# stm32_usbserial.net
KiCad netlist of a schematic drawn in EAGLE
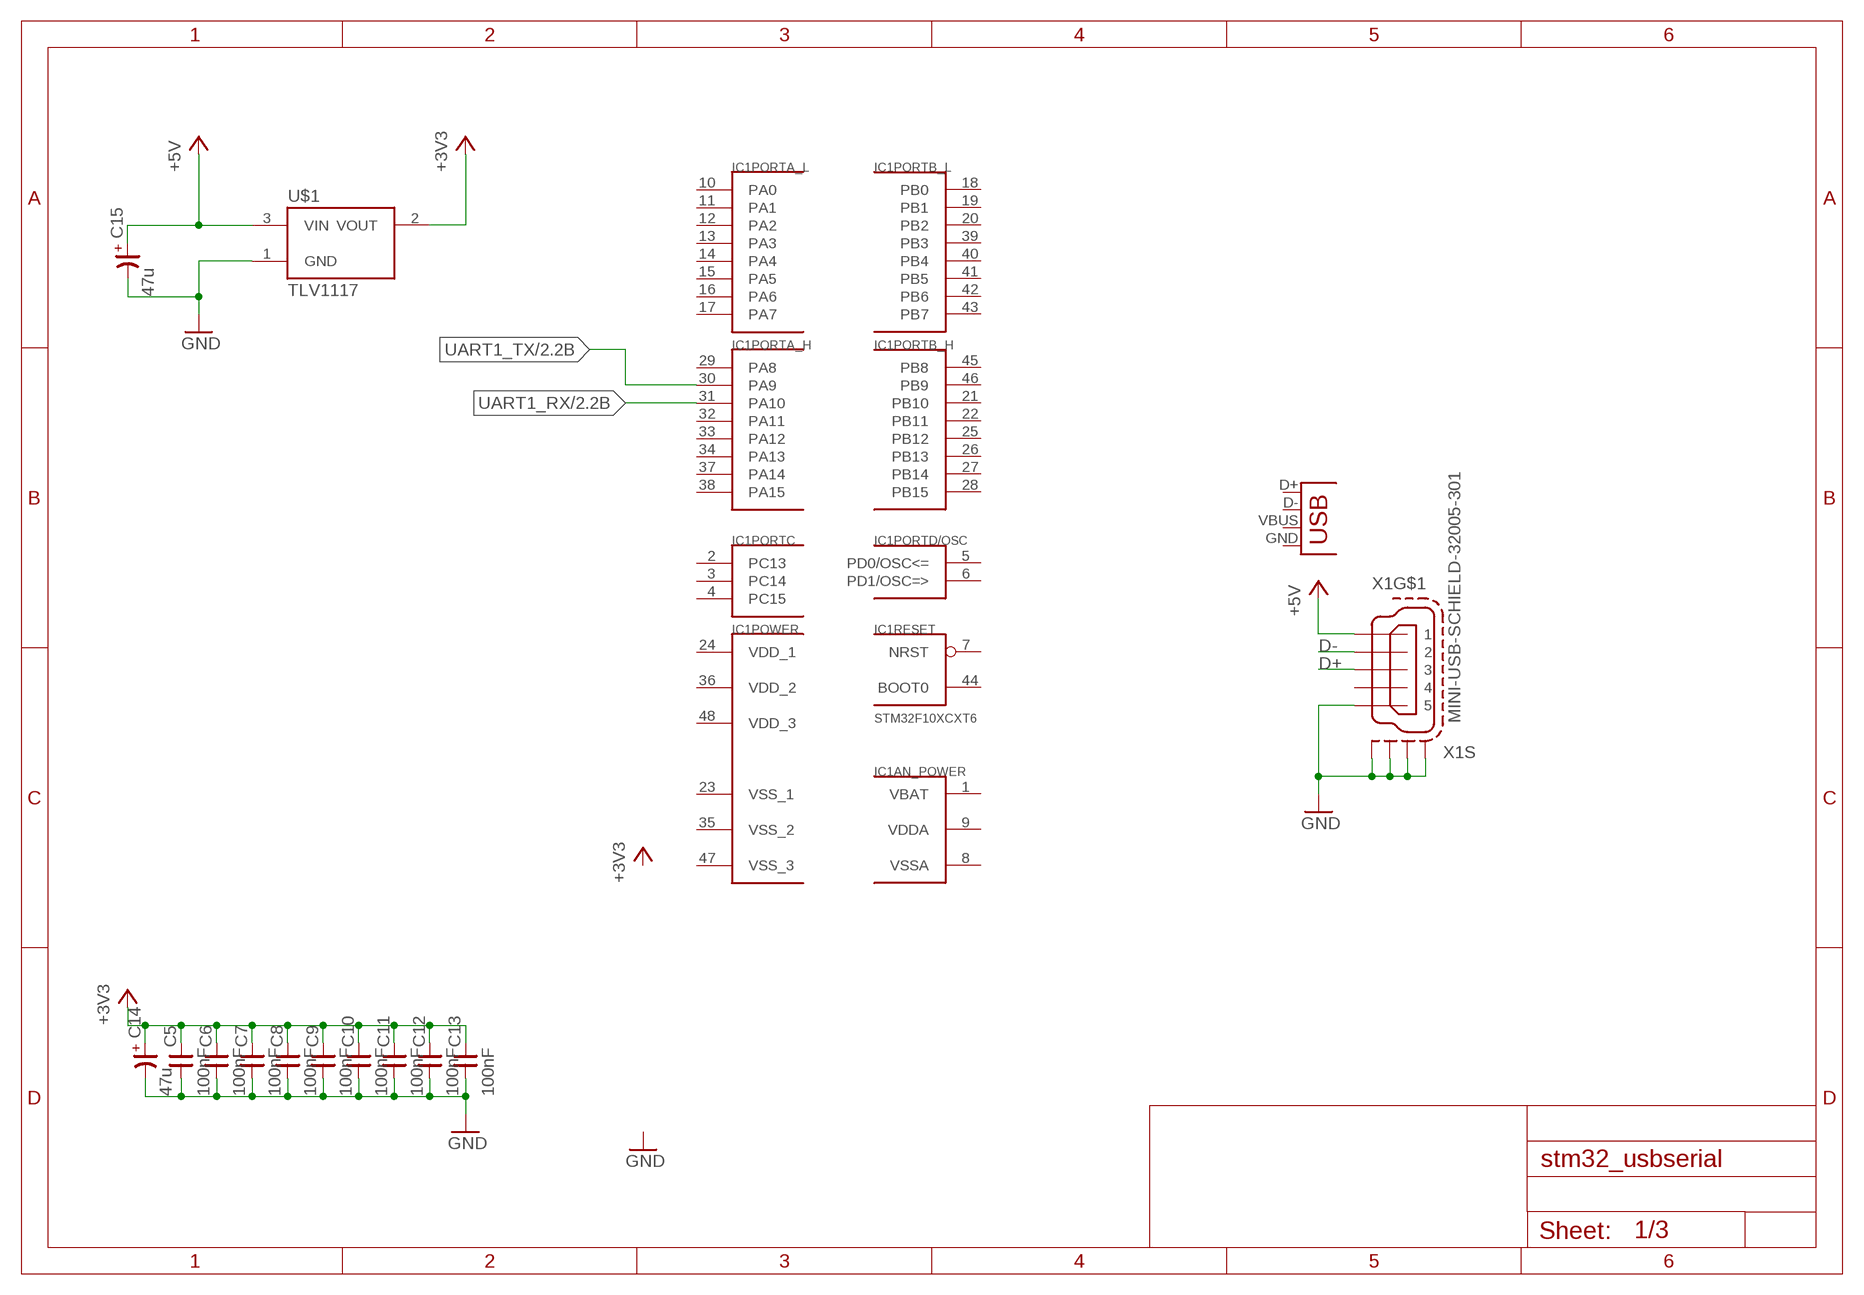
[diagram p0: schematic, sheet 1]
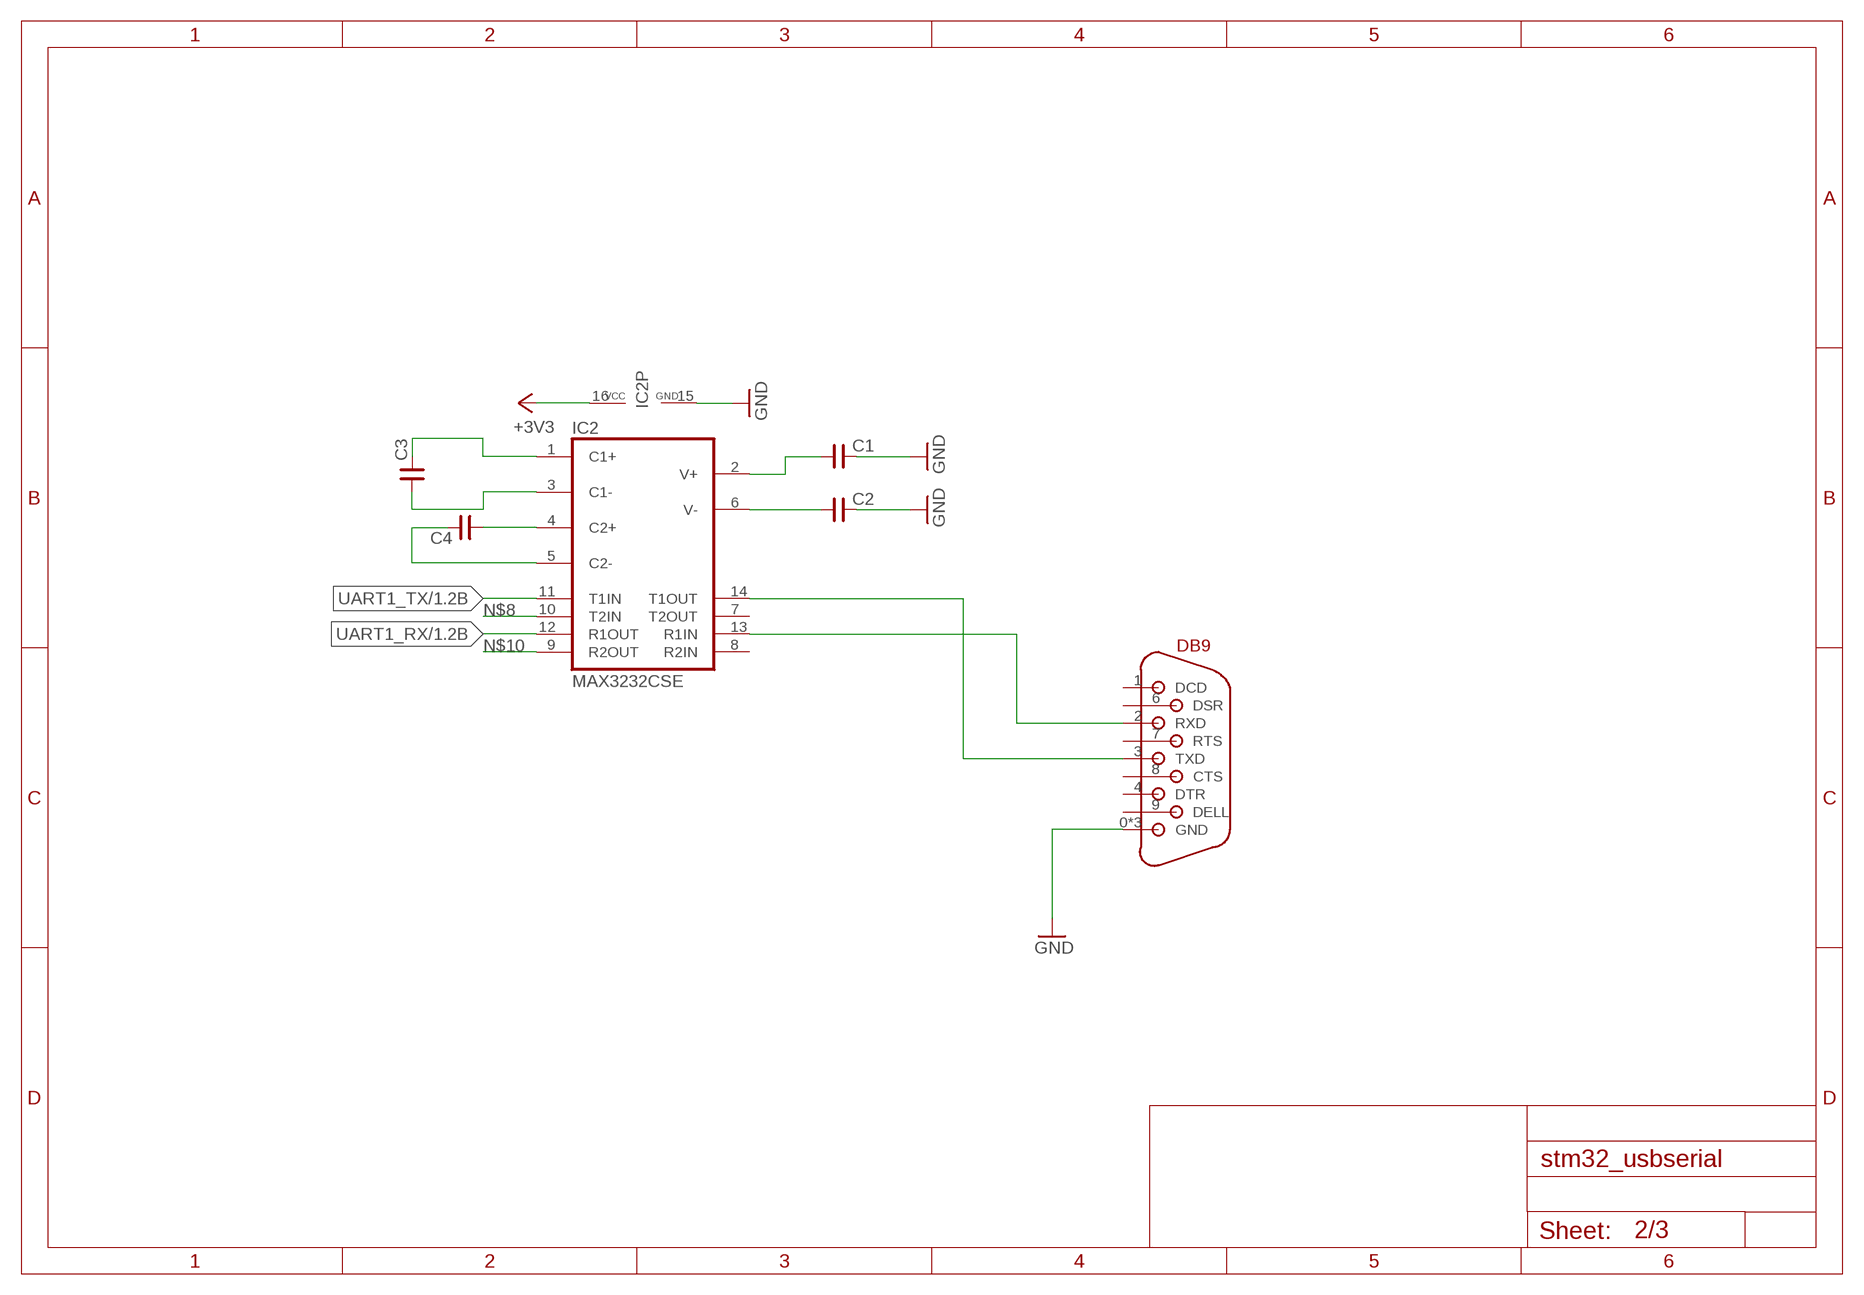
[diagram p1: schematic, sheet 2]

(export (version "E")
  (design (tool "Eeschema 10.0.6"))
  (components
    (comp (ref "C1")
      (value "CNP-0805")
      (footprint "eagle-import:0805")
      (libsource (lib "eagle-import") (part "CNP-0805"))
    )
    (comp (ref "C2")
      (value "CNP-0805")
      (footprint "eagle-import:0805")
      (libsource (lib "eagle-import") (part "CNP-0805"))
    )
    (comp (ref "C3")
      (value "CNP-0805")
      (footprint "eagle-import:0805")
      (libsource (lib "eagle-import") (part "CNP-0805"))
    )
    (comp (ref "C4")
      (value "CNP-0805")
      (footprint "eagle-import:0805")
      (libsource (lib "eagle-import") (part "CNP-0805"))
    )
    (comp (ref "IC2")
      (value "MAX3232CSE")
      (footprint "eagle-import:SO16")
      (libsource (lib "eagle-import") (part "MAX3232SEC"))
    )
    (comp (ref "U$2")
      (value "DB9-FMALE'FMALE'")
      (footprint "eagle-import:DB9-FMALE")
      (libsource (lib "eagle-import") (part "DB9-'FMALE'FMALE"))
    )
    (comp (ref "C5")
      (value "100nF")
      (footprint "eagle-import:0805")
      (libsource (lib "eagle-import") (part "CNP-0805"))
    )
    (comp (ref "C6")
      (value "100nF")
      (footprint "eagle-import:0805")
      (libsource (lib "eagle-import") (part "CNP-0805"))
    )
    (comp (ref "C7")
      (value "100nF")
      (footprint "eagle-import:0805")
      (libsource (lib "eagle-import") (part "CNP-0805"))
    )
    (comp (ref "C8")
      (value "100nF")
      (footprint "eagle-import:0805")
      (libsource (lib "eagle-import") (part "CNP-0805"))
    )
    (comp (ref "C9")
      (value "100nF")
      (footprint "eagle-import:0805")
      (libsource (lib "eagle-import") (part "CNP-0805"))
    )
    (comp (ref "C10")
      (value "100nF")
      (footprint "eagle-import:0805")
      (libsource (lib "eagle-import") (part "CNP-0805"))
    )
    (comp (ref "C11")
      (value "100nF")
      (footprint "eagle-import:0805")
      (libsource (lib "eagle-import") (part "CNP-0805"))
    )
    (comp (ref "C12")
      (value "100nF")
      (footprint "eagle-import:0805")
      (libsource (lib "eagle-import") (part "CNP-0805"))
    )
    (comp (ref "C13")
      (value "100nF")
      (footprint "eagle-import:0805")
      (libsource (lib "eagle-import") (part "CNP-0805"))
    )
    (comp (ref "C14")
      (value "47u")
      (footprint "eagle-import:153CLV-1012")
      (libsource (lib "eagle-import") (part "CP-153CLV-1012"))
    )
    (comp (ref "C15")
      (value "47u")
      (footprint "eagle-import:153CLV-1012")
      (libsource (lib "eagle-import") (part "CP-153CLV-1012"))
    )
    (comp (ref "IC1")
      (value "STM32F10XCXT6")
      (footprint "eagle-import:TQFP48")
      (libsource (lib "eagle-import") (part "STM32F10XCXT6"))
    )
    (comp (ref "U$1")
      (value "TLV1117")
      (footprint "eagle-import:SOT223")
      (libsource (lib "eagle-import") (part "TLV1117"))
    )
    (comp (ref "X1")
      (value "MINI-USB-SCHIELD-32005-301")
      (footprint "eagle-import:32005-301")
      (libsource (lib "eagle-import") (part "MINI-USB-SCHIELD-32005-301"))
    )
    (comp (ref "X2")
      (value "USB-MB-S")
      (footprint "eagle-import:USB-MB-S")
      (libsource (lib "eagle-import") (part "USB-MB-S"))
    )
  )
  (nets
    (net (code "1") (name "+3V3") (class "Default")
      (node (ref "C10") (pin "2") (pinfunction "2_2") (pintype "passive"))
      (node (ref "C11") (pin "2") (pinfunction "2_2") (pintype "passive"))
      (node (ref "C12") (pin "2") (pinfunction "2_2") (pintype "passive"))
      (node (ref "C13") (pin "2") (pinfunction "2_2") (pintype "passive"))
      (node (ref "C14") (pin "+") (pinfunction "+_+") (pintype "passive"))
      (node (ref "C5") (pin "2") (pinfunction "2_2") (pintype "passive"))
      (node (ref "C6") (pin "2") (pinfunction "2_2") (pintype "passive"))
      (node (ref "C7") (pin "2") (pinfunction "2_2") (pintype "passive"))
      (node (ref "C8") (pin "2") (pinfunction "2_2") (pintype "passive"))
      (node (ref "C9") (pin "2") (pinfunction "2_2") (pintype "passive"))
      (node (ref "IC2") (pin "16") (pinfunction "VCC_16") (pintype "power_in"))
      (node (ref "U$1") (pin "2") (pinfunction "VOUT_2") (pintype "power_in"))
      (node (ref "U$1") (pin "4") (pinfunction "VOUT2_4") (pintype "power_in"))
    )
    (net (code "2") (name "+5V") (class "Default")
      (node (ref "C15") (pin "+") (pinfunction "+_+") (pintype "passive"))
      (node (ref "U$1") (pin "3") (pinfunction "VIN_3") (pintype "power_in"))
      (node (ref "X1") (pin "1") (pinfunction "1_1") (pintype "passive"))
    )
    (net (code "3") (name "D+") (class "Default")
      (node (ref "X1") (pin "3") (pinfunction "3_3") (pintype "passive"))
    )
    (net (code "4") (name "D-") (class "Default")
      (node (ref "X1") (pin "2") (pinfunction "2_2") (pintype "passive"))
    )
    (net (code "5") (name "GND") (class "Default")
      (node (ref "C1") (pin "2") (pinfunction "2_2") (pintype "passive"))
      (node (ref "C10") (pin "1") (pinfunction "1_1") (pintype "passive"))
      (node (ref "C11") (pin "1") (pinfunction "1_1") (pintype "passive"))
      (node (ref "C12") (pin "1") (pinfunction "1_1") (pintype "passive"))
      (node (ref "C13") (pin "1") (pinfunction "1_1") (pintype "passive"))
      (node (ref "C14") (pin "-") (pinfunction "-_-") (pintype "passive"))
      (node (ref "C15") (pin "-") (pinfunction "-_-") (pintype "passive"))
      (node (ref "C2") (pin "2") (pinfunction "2_2") (pintype "passive"))
      (node (ref "C5") (pin "1") (pinfunction "1_1") (pintype "passive"))
      (node (ref "C6") (pin "1") (pinfunction "1_1") (pintype "passive"))
      (node (ref "C7") (pin "1") (pinfunction "1_1") (pintype "passive"))
      (node (ref "C8") (pin "1") (pinfunction "1_1") (pintype "passive"))
      (node (ref "C9") (pin "1") (pinfunction "1_1") (pintype "passive"))
      (node (ref "IC2") (pin "15") (pinfunction "GND_15") (pintype "power_in"))
      (node (ref "U$1") (pin "1") (pinfunction "GND_1") (pintype "power_in"))
      (node (ref "U$2") (pin "0") (pinfunction "GND_0") (pintype "power_in"))
      (node (ref "U$2") (pin "10") (pinfunction "GND_10") (pintype "power_in"))
      (node (ref "U$2") (pin "5") (pinfunction "GND_5") (pintype "power_in"))
      (node (ref "X1") (pin "5") (pinfunction "5_5") (pintype "passive"))
      (node (ref "X1") (pin "M1") (pinfunction "S1_M1") (pintype "passive"))
      (node (ref "X1") (pin "M2") (pinfunction "S2_M2") (pintype "passive"))
      (node (ref "X1") (pin "M3") (pinfunction "S3_M3") (pintype "passive"))
      (node (ref "X1") (pin "M4") (pinfunction "S4_M4") (pintype "passive"))
    )
    (net (code "6") (name "N$8") (class "Default")
      (node (ref "IC2") (pin "10") (pinfunction "T2IN_10") (pintype "input"))
    )
    (net (code "7") (name "N$10") (class "Default")
      (node (ref "IC2") (pin "9") (pinfunction "R2OUT_9") (pintype "output"))
    )
    (net (code "8") (name "Net-(IC2A-C1+)") (class "Default")
      (node (ref "C3") (pin "2") (pinfunction "2_2") (pintype "passive"))
      (node (ref "IC2") (pin "1") (pinfunction "C1+_1") (pintype "bidirectional"))
    )
    (net (code "9") (name "Net-(IC2A-C1-)") (class "Default")
      (node (ref "C3") (pin "1") (pinfunction "1_1") (pintype "passive"))
      (node (ref "IC2") (pin "3") (pinfunction "C1-_3") (pintype "bidirectional"))
    )
    (net (code "10") (name "Net-(IC2A-C2+)") (class "Default")
      (node (ref "C4") (pin "1") (pinfunction "1_1") (pintype "passive"))
      (node (ref "IC2") (pin "4") (pinfunction "C2+_4") (pintype "bidirectional"))
    )
    (net (code "11") (name "Net-(IC2A-C2-)") (class "Default")
      (node (ref "C4") (pin "2") (pinfunction "2_2") (pintype "passive"))
      (node (ref "IC2") (pin "5") (pinfunction "C2-_5") (pintype "bidirectional"))
    )
    (net (code "12") (name "Net-(IC2A-R1IN)") (class "Default")
      (node (ref "IC2") (pin "13") (pinfunction "R1IN_13") (pintype "input"))
      (node (ref "U$2") (pin "2") (pinfunction "RXD_2") (pintype "bidirectional"))
    )
    (net (code "13") (name "Net-(IC2A-T1OUT)") (class "Default")
      (node (ref "IC2") (pin "14") (pinfunction "T1OUT_14") (pintype "output"))
      (node (ref "U$2") (pin "3") (pinfunction "TXD_3") (pintype "bidirectional"))
    )
    (net (code "14") (name "Net-(IC2A-V+)") (class "Default")
      (node (ref "C1") (pin "1") (pinfunction "1_1") (pintype "passive"))
      (node (ref "IC2") (pin "2") (pinfunction "V+_2") (pintype "bidirectional"))
    )
    (net (code "15") (name "Net-(IC2A-V-)") (class "Default")
      (node (ref "C2") (pin "1") (pinfunction "1_1") (pintype "passive"))
      (node (ref "IC2") (pin "6") (pinfunction "V-_6") (pintype "bidirectional"))
    )
    (net (code "16") (name "UART1_RX") (class "Default")
      (node (ref "IC1") (pin "31") (pinfunction "PA10_31") (pintype "bidirectional"))
      (node (ref "IC2") (pin "12") (pinfunction "R1OUT_12") (pintype "output"))
    )
    (net (code "17") (name "UART1_TX") (class "Default")
      (node (ref "IC1") (pin "30") (pinfunction "PA9_30") (pintype "bidirectional"))
      (node (ref "IC2") (pin "11") (pinfunction "T1IN_11") (pintype "input"))
    )
    (net (code "18") (name "VBAT") (class "Default")
      (node (ref "IC1") (pin "1") (pinfunction "VBAT_1") (pintype "power_in"))
    )
    (net (code "19") (name "VDDA") (class "Default")
      (node (ref "IC1") (pin "9") (pinfunction "VDDA_9") (pintype "power_in"))
    )
    (net (code "20") (name "VDD_1") (class "Default")
      (node (ref "IC1") (pin "24") (pinfunction "VDD_1_24") (pintype "power_in"))
    )
    (net (code "21") (name "VDD_2") (class "Default")
      (node (ref "IC1") (pin "36") (pinfunction "VDD_2_36") (pintype "power_in"))
    )
    (net (code "22") (name "VDD_3") (class "Default")
      (node (ref "IC1") (pin "48") (pinfunction "VDD_3_48") (pintype "power_in"))
    )
    (net (code "23") (name "VSSA") (class "Default")
      (node (ref "IC1") (pin "8") (pinfunction "VSSA_8") (pintype "power_in"))
    )
    (net (code "24") (name "VSS_1") (class "Default")
      (node (ref "IC1") (pin "23") (pinfunction "VSS_1_23") (pintype "power_in"))
    )
    (net (code "25") (name "VSS_2") (class "Default")
      (node (ref "IC1") (pin "35") (pinfunction "VSS_2_35") (pintype "power_in"))
    )
    (net (code "26") (name "VSS_3") (class "Default")
      (node (ref "IC1") (pin "47") (pinfunction "VSS_3_47") (pintype "power_in"))
    )
    (net (code "27") (name "unconnected-(IC1B-PA8-Pad29)") (class "Default")
      (node (ref "IC1") (pin "29") (pinfunction "PA8_29") (pintype "bidirectional"))
    )
    (net (code "28") (name "unconnected-(IC1B-PA11-Pad32)") (class "Default")
      (node (ref "IC1") (pin "32") (pinfunction "PA11_32") (pintype "bidirectional"))
    )
    (net (code "29") (name "unconnected-(IC1B-PA12-Pad33)") (class "Default")
      (node (ref "IC1") (pin "33") (pinfunction "PA12_33") (pintype "bidirectional"))
    )
    (net (code "30") (name "unconnected-(IC1B-PA13-Pad34)") (class "Default")
      (node (ref "IC1") (pin "34") (pinfunction "PA13_34") (pintype "bidirectional"))
    )
    (net (code "31") (name "unconnected-(IC1B-PA14-Pad37)") (class "Default")
      (node (ref "IC1") (pin "37") (pinfunction "PA14_37") (pintype "bidirectional"))
    )
    (net (code "32") (name "unconnected-(IC1B-PA15-Pad38)") (class "Default")
      (node (ref "IC1") (pin "38") (pinfunction "PA15_38") (pintype "bidirectional"))
    )
    (net (code "33") (name "unconnected-(IC1C-PA0-Pad10)") (class "Default")
      (node (ref "IC1") (pin "10") (pinfunction "PA0_10") (pintype "bidirectional"))
    )
    (net (code "34") (name "unconnected-(IC1C-PA1-Pad11)") (class "Default")
      (node (ref "IC1") (pin "11") (pinfunction "PA1_11") (pintype "bidirectional"))
    )
    (net (code "35") (name "unconnected-(IC1C-PA2-Pad12)") (class "Default")
      (node (ref "IC1") (pin "12") (pinfunction "PA2_12") (pintype "bidirectional"))
    )
    (net (code "36") (name "unconnected-(IC1C-PA3-Pad13)") (class "Default")
      (node (ref "IC1") (pin "13") (pinfunction "PA3_13") (pintype "bidirectional"))
    )
    (net (code "37") (name "unconnected-(IC1C-PA4-Pad14)") (class "Default")
      (node (ref "IC1") (pin "14") (pinfunction "PA4_14") (pintype "bidirectional"))
    )
    (net (code "38") (name "unconnected-(IC1C-PA5-Pad15)") (class "Default")
      (node (ref "IC1") (pin "15") (pinfunction "PA5_15") (pintype "bidirectional"))
    )
    (net (code "39") (name "unconnected-(IC1C-PA6-Pad16)") (class "Default")
      (node (ref "IC1") (pin "16") (pinfunction "PA6_16") (pintype "bidirectional"))
    )
    (net (code "40") (name "unconnected-(IC1C-PA7-Pad17)") (class "Default")
      (node (ref "IC1") (pin "17") (pinfunction "PA7_17") (pintype "bidirectional"))
    )
    (net (code "41") (name "unconnected-(IC1D-PB8-Pad45)") (class "Default")
      (node (ref "IC1") (pin "45") (pinfunction "PB8_45") (pintype "bidirectional"))
    )
    (net (code "42") (name "unconnected-(IC1D-PB9-Pad46)") (class "Default")
      (node (ref "IC1") (pin "46") (pinfunction "PB9_46") (pintype "bidirectional"))
    )
    (net (code "43") (name "unconnected-(IC1D-PB10-Pad21)") (class "Default")
      (node (ref "IC1") (pin "21") (pinfunction "PB10_21") (pintype "bidirectional"))
    )
    (net (code "44") (name "unconnected-(IC1D-PB11-Pad22)") (class "Default")
      (node (ref "IC1") (pin "22") (pinfunction "PB11_22") (pintype "bidirectional"))
    )
    (net (code "45") (name "unconnected-(IC1D-PB12-Pad25)") (class "Default")
      (node (ref "IC1") (pin "25") (pinfunction "PB12_25") (pintype "bidirectional"))
    )
    (net (code "46") (name "unconnected-(IC1D-PB13-Pad26)") (class "Default")
      (node (ref "IC1") (pin "26") (pinfunction "PB13_26") (pintype "bidirectional"))
    )
    (net (code "47") (name "unconnected-(IC1D-PB14-Pad27)") (class "Default")
      (node (ref "IC1") (pin "27") (pinfunction "PB14_27") (pintype "bidirectional"))
    )
    (net (code "48") (name "unconnected-(IC1D-PB15-Pad28)") (class "Default")
      (node (ref "IC1") (pin "28") (pinfunction "PB15_28") (pintype "bidirectional"))
    )
    (net (code "49") (name "unconnected-(IC1E-PB0-Pad18)") (class "Default")
      (node (ref "IC1") (pin "18") (pinfunction "PB0_18") (pintype "bidirectional"))
    )
    (net (code "50") (name "unconnected-(IC1E-PB1-Pad19)") (class "Default")
      (node (ref "IC1") (pin "19") (pinfunction "PB1_19") (pintype "bidirectional"))
    )
    (net (code "51") (name "unconnected-(IC1E-PB2-Pad20)") (class "Default")
      (node (ref "IC1") (pin "20") (pinfunction "PB2_20") (pintype "bidirectional"))
    )
    (net (code "52") (name "unconnected-(IC1E-PB3-Pad39)") (class "Default")
      (node (ref "IC1") (pin "39") (pinfunction "PB3_39") (pintype "bidirectional"))
    )
    (net (code "53") (name "unconnected-(IC1E-PB4-Pad40)") (class "Default")
      (node (ref "IC1") (pin "40") (pinfunction "PB4_40") (pintype "bidirectional"))
    )
    (net (code "54") (name "unconnected-(IC1E-PB5-Pad41)") (class "Default")
      (node (ref "IC1") (pin "41") (pinfunction "PB5_41") (pintype "bidirectional"))
    )
    (net (code "55") (name "unconnected-(IC1E-PB6-Pad42)") (class "Default")
      (node (ref "IC1") (pin "42") (pinfunction "PB6_42") (pintype "bidirectional"))
    )
    (net (code "56") (name "unconnected-(IC1E-PB7-Pad43)") (class "Default")
      (node (ref "IC1") (pin "43") (pinfunction "PB7_43") (pintype "bidirectional"))
    )
    (net (code "57") (name "unconnected-(IC1F-PC13-Pad2)") (class "Default")
      (node (ref "IC1") (pin "2") (pinfunction "PC13_2") (pintype "bidirectional"))
    )
    (net (code "58") (name "unconnected-(IC1F-PC14-Pad3)") (class "Default")
      (node (ref "IC1") (pin "3") (pinfunction "PC14_3") (pintype "bidirectional"))
    )
    (net (code "59") (name "unconnected-(IC1F-PC15-Pad4)") (class "Default")
      (node (ref "IC1") (pin "4") (pinfunction "PC15_4") (pintype "bidirectional"))
    )
    (net (code "60") (name "unconnected-(IC1G-PD0{slash}OSC<=-Pad5)") (class "Default")
      (node (ref "IC1") (pin "5") (pinfunction "PD0/OSC<=_5") (pintype "bidirectional"))
    )
    (net (code "61") (name "unconnected-(IC1G-PD1{slash}OSC=>-Pad6)") (class "Default")
      (node (ref "IC1") (pin "6") (pinfunction "PD1/OSC=>_6") (pintype "bidirectional"))
    )
    (net (code "62") (name "unconnected-(IC1I-BOOT0-Pad44)") (class "Default")
      (node (ref "IC1") (pin "44") (pinfunction "BOOT0_44") (pintype "input"))
    )
    (net (code "63") (name "unconnected-(IC1I-NRST-Pad7)") (class "Default")
      (node (ref "IC1") (pin "7") (pinfunction "NRST_7") (pintype "input"))
    )
    (net (code "64") (name "unconnected-(IC2A-R2IN-Pad8)") (class "Default")
      (node (ref "IC2") (pin "8") (pinfunction "R2IN_8") (pintype "input"))
    )
    (net (code "65") (name "unconnected-(IC2A-T2OUT-Pad7)") (class "Default")
      (node (ref "IC2") (pin "7") (pinfunction "T2OUT_7") (pintype "output"))
    )
    (net (code "66") (name "unconnected-(U$2-CTS-Pad8)") (class "Default")
      (node (ref "U$2") (pin "8") (pinfunction "CTS_8") (pintype "bidirectional"))
    )
    (net (code "67") (name "unconnected-(U$2-DCD-Pad1)") (class "Default")
      (node (ref "U$2") (pin "1") (pinfunction "DCD_1") (pintype "bidirectional"))
    )
    (net (code "68") (name "unconnected-(U$2-DELL-Pad9)") (class "Default")
      (node (ref "U$2") (pin "9") (pinfunction "DELL_9") (pintype "bidirectional"))
    )
    (net (code "69") (name "unconnected-(U$2-DSR-Pad6)") (class "Default")
      (node (ref "U$2") (pin "6") (pinfunction "DSR_6") (pintype "bidirectional"))
    )
    (net (code "70") (name "unconnected-(U$2-DTR-Pad4)") (class "Default")
      (node (ref "U$2") (pin "4") (pinfunction "DTR_4") (pintype "bidirectional"))
    )
    (net (code "71") (name "unconnected-(U$2-RTS-Pad7)") (class "Default")
      (node (ref "U$2") (pin "7") (pinfunction "RTS_7") (pintype "bidirectional"))
    )
    (net (code "72") (name "unconnected-(X1-Pad4)") (class "Default")
      (node (ref "X1") (pin "4") (pinfunction "4_4") (pintype "passive"))
    )
    (net (code "73") (name "unconnected-(X2-PadD+)") (class "Default")
      (node (ref "X2") (pin "D+") (pinfunction "D+_D+") (pintype "bidirectional"))
    )
    (net (code "74") (name "unconnected-(X2-PadD-)") (class "Default")
      (node (ref "X2") (pin "D-") (pinfunction "D-_D-") (pintype "bidirectional"))
    )
    (net (code "75") (name "unconnected-(X2-PadGND)") (class "Default")
      (node (ref "X2") (pin "GND") (pinfunction "GND_GND") (pintype "bidirectional"))
    )
    (net (code "76") (name "unconnected-(X2-PadVBUS)") (class "Default")
      (node (ref "X2") (pin "VBUS") (pinfunction "VBUS_VBUS") (pintype "bidirectional"))
    )
  )
)
